# InkTime_Schematic.net
KiCad netlist of a schematic drawn in EAGLE
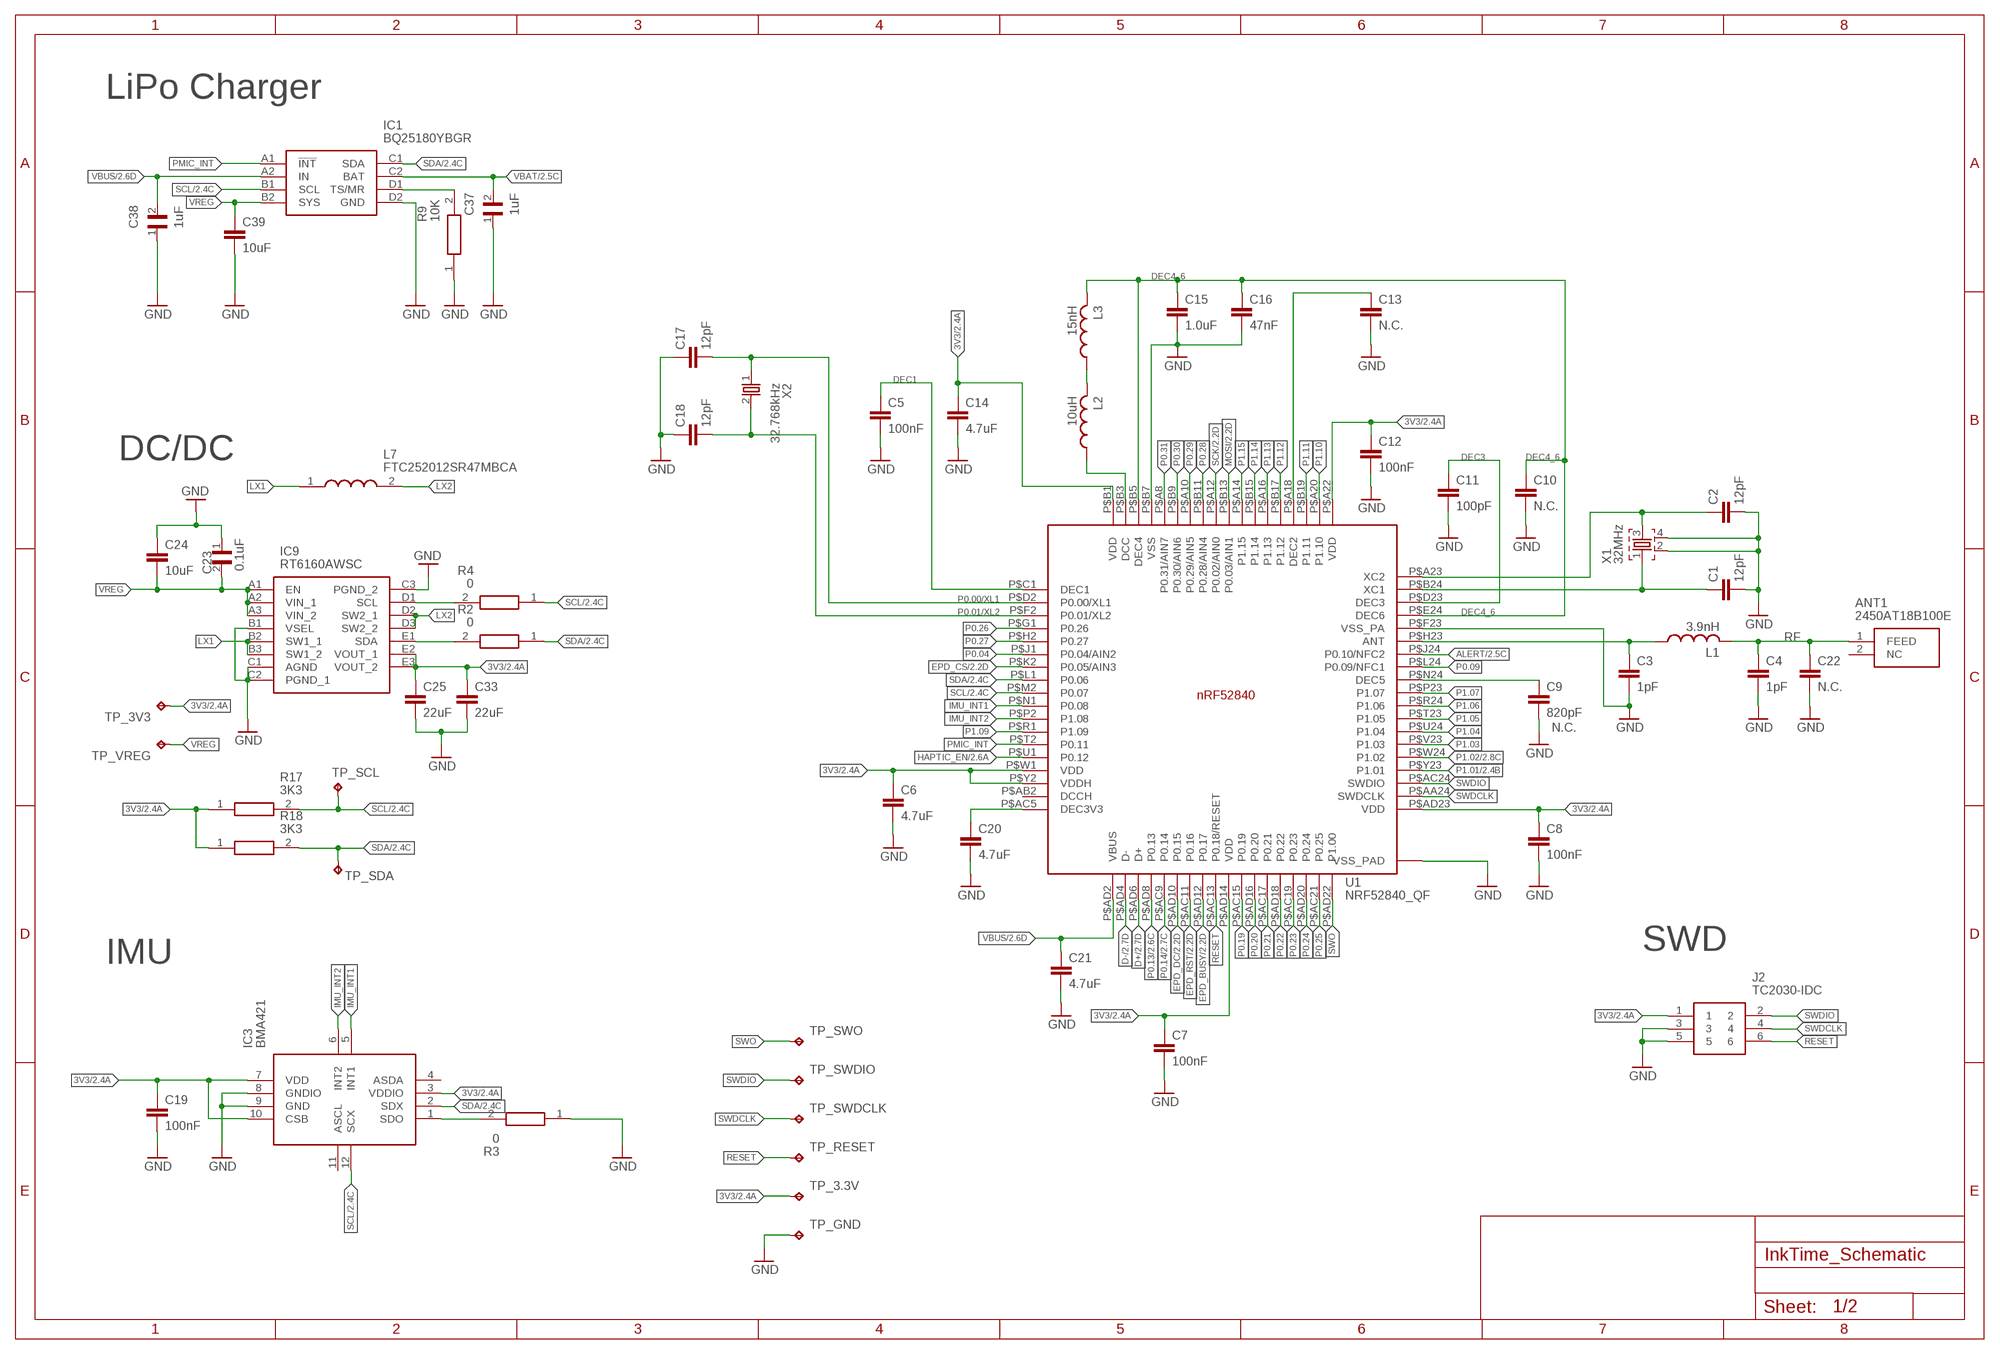
[diagram p0: schematic, sheet 1]
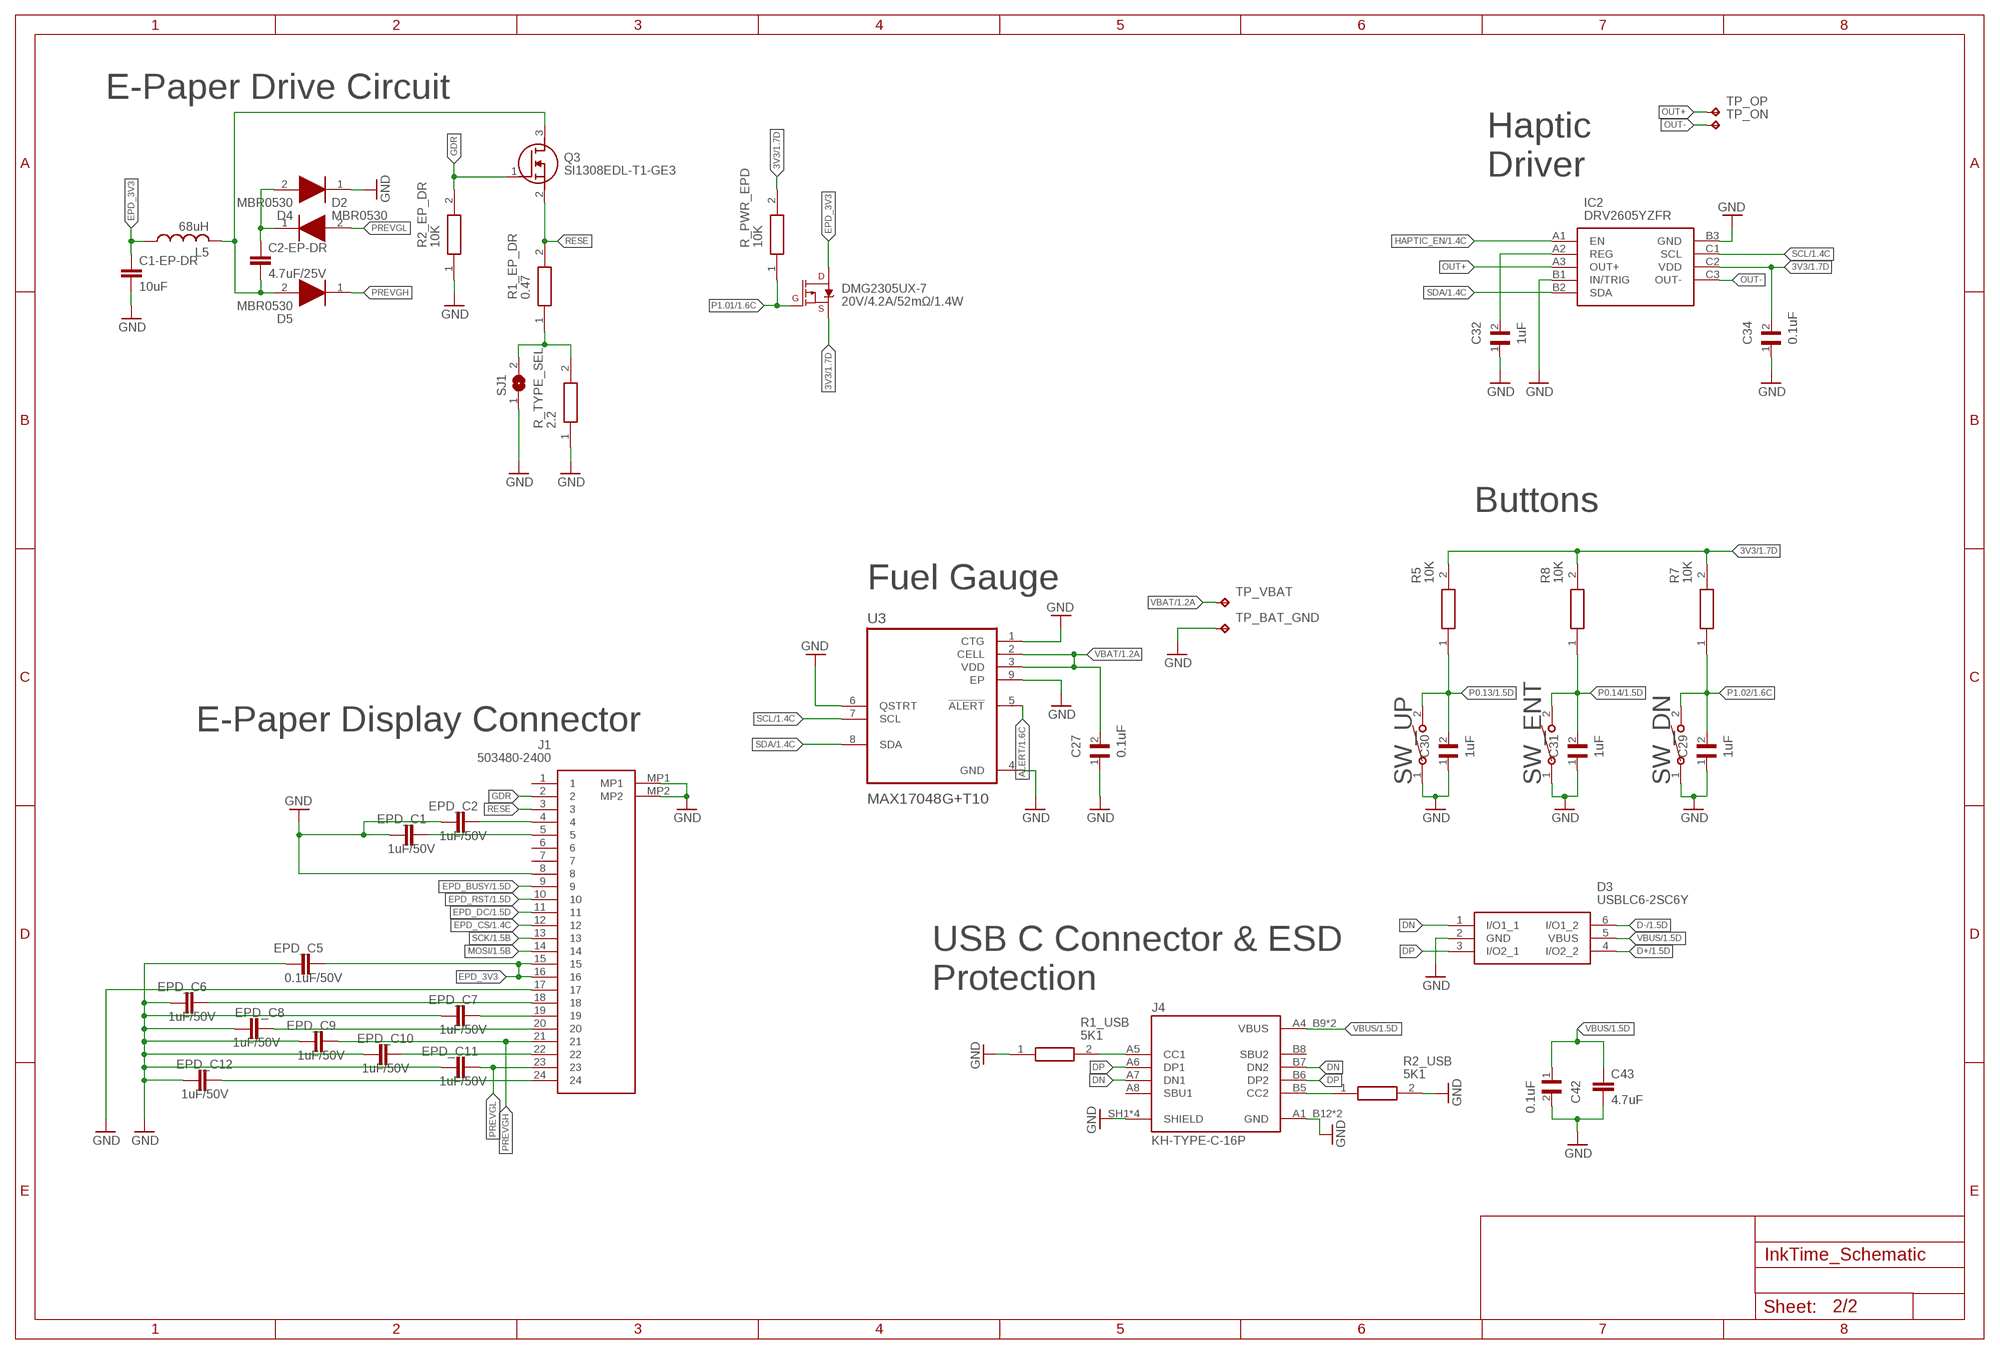
[diagram p1: schematic, sheet 2]

(export (version "E")
  (design (tool "Eeschema 10.0.6"))
  (components
    (comp (ref "ANT1")
      (value "2450AT18B100E")
      (footprint "eagle-import:2450AT18B100E_ANTC3216X140N")
      (fields (field (name "MOUSER_PART_NUMBER") "609-2450AT18B100E"))
      (libsource (lib "eagle-import") (part "2450AT18B100E_2450AT18B100E"))
    )
    (comp (ref "C1")
      (value "12pF")
      (footprint "eagle-import:GRM011R60J152KE01L_2_CAPC0201X13N")
      (libsource (lib "eagle-import") (part "NORDIC_NRF_3_CAPACITOR_0201_L"))
    )
    (comp (ref "C2")
      (value "12pF")
      (footprint "eagle-import:GRM011R60J152KE01L_2_CAPC0201X13N")
      (libsource (lib "eagle-import") (part "NORDIC_NRF_3_CAPACITOR_0201_L"))
    )
    (comp (ref "C3")
      (value "1pF")
      (footprint "eagle-import:GRM011R60J152KE01L_2_CAPC0201X13N")
      (libsource (lib "eagle-import") (part "NORDIC_NRF_3_CAPACITOR_0201_L"))
    )
    (comp (ref "C4")
      (value "1pF")
      (footprint "eagle-import:GRM011R60J152KE01L_2_CAPC0201X13N")
      (libsource (lib "eagle-import") (part "NORDIC_NRF_3_CAPACITOR_0201_L"))
    )
    (comp (ref "C5")
      (value "100nF")
      (footprint "eagle-import:GRM011R60J152KE01L_2_CAPC0201X13N")
      (libsource (lib "eagle-import") (part "NORDIC_NRF_3_CAPACITOR_0201_L"))
    )
    (comp (ref "C6")
      (value "4.7uF")
      (footprint "eagle-import:NORDIC_NRF_3_RESC0402_L")
      (libsource (lib "eagle-import") (part "NORDIC_NRF_3_CAPACITOR_0402_L"))
    )
    (comp (ref "C7")
      (value "100nF")
      (footprint "eagle-import:GRM011R60J152KE01L_2_CAPC0201X13N")
      (libsource (lib "eagle-import") (part "NORDIC_NRF_3_CAPACITOR_0201_L"))
    )
    (comp (ref "C8")
      (value "100nF")
      (footprint "eagle-import:GRM011R60J152KE01L_2_CAPC0201X13N")
      (libsource (lib "eagle-import") (part "NORDIC_NRF_3_CAPACITOR_0201_L"))
    )
    (comp (ref "C9")
      (value "820pF")
      (footprint "eagle-import:GRM011R60J152KE01L_2_CAPC0201X13N")
      (libsource (lib "eagle-import") (part "NORDIC_NRF_3_CAPACITOR_0201_L"))
    )
    (comp (ref "C10")
      (value "N.C.")
      (footprint "eagle-import:GRM011R60J152KE01L_2_CAPC0201X13N")
      (libsource (lib "eagle-import") (part "NORDIC_NRF_3_CAPACITOR_0201_L"))
    )
    (comp (ref "C11")
      (value "100pF")
      (footprint "eagle-import:GRM011R60J152KE01L_2_CAPC0201X13N")
      (libsource (lib "eagle-import") (part "NORDIC_NRF_3_CAPACITOR_0201_L"))
    )
    (comp (ref "C12")
      (value "100nF")
      (footprint "eagle-import:GRM011R60J152KE01L_2_CAPC0201X13N")
      (libsource (lib "eagle-import") (part "NORDIC_NRF_3_CAPACITOR_0201_L"))
    )
    (comp (ref "C13")
      (value "N.C.")
      (footprint "eagle-import:GRM011R60J152KE01L_2_CAPC0201X13N")
      (libsource (lib "eagle-import") (part "NORDIC_NRF_3_CAPACITOR_0201_L"))
    )
    (comp (ref "C14")
      (value "4.7uF")
      (footprint "eagle-import:NORDIC_NRF_3_RESC0402_L")
      (libsource (lib "eagle-import") (part "NORDIC_NRF_3_CAPACITOR_0402_L"))
    )
    (comp (ref "C15")
      (value "1.0uF")
      (footprint "eagle-import:NORDIC_NRF_3_RESC0402_L")
      (libsource (lib "eagle-import") (part "NORDIC_NRF_3_CAPACITOR_0402_L"))
    )
    (comp (ref "C16")
      (value "47nF")
      (footprint "eagle-import:GRM011R60J152KE01L_2_CAPC0201X13N")
      (libsource (lib "eagle-import") (part "NORDIC_NRF_3_CAPACITOR_0201_L"))
    )
    (comp (ref "C17")
      (value "12pF")
      (footprint "eagle-import:GRM011R60J152KE01L_2_CAPC0201X13N")
      (libsource (lib "eagle-import") (part "NORDIC_NRF_3_CAPACITOR_0201_L"))
    )
    (comp (ref "C18")
      (value "12pF")
      (footprint "eagle-import:GRM011R60J152KE01L_2_CAPC0201X13N")
      (libsource (lib "eagle-import") (part "NORDIC_NRF_3_CAPACITOR_0201_L"))
    )
    (comp (ref "C19")
      (value "100nF")
      (footprint "eagle-import:GRM011R60J152KE01L_2_CAPC0201X13N")
      (libsource (lib "eagle-import") (part "NORDIC_NRF_3_CAPACITOR_0201_L"))
    )
    (comp (ref "C20")
      (value "4.7uF")
      (footprint "eagle-import:NORDIC_NRF_3_RESC0402_L")
      (libsource (lib "eagle-import") (part "NORDIC_NRF_3_CAPACITOR_0402_L"))
    )
    (comp (ref "C21")
      (value "4.7uF")
      (footprint "eagle-import:NORDIC_NRF_3_RESC0402_L")
      (libsource (lib "eagle-import") (part "NORDIC_NRF_3_CAPACITOR_0402_L"))
    )
    (comp (ref "C22")
      (value "N.C.")
      (footprint "eagle-import:GRM011R60J152KE01L_2_CAPC0201X13N")
      (libsource (lib "eagle-import") (part "NORDIC_NRF_3_CAPACITOR_0201_L"))
    )
    (comp (ref "C23")
      (value "0.1uF")
      (footprint "eagle-import:GRM011R60J152KE01L_2_CAPC0201X13N")
      (fields (field (name "MF") "Murata") (field (name "MP") "GRM011R60J152KE01L"))
      (libsource (lib "eagle-import") (part "GRM011R60J152KE01L_2_GRM011R60J152KE01L"))
    )
    (comp (ref "C24")
      (value "10uF")
      (footprint "eagle-import:NORDIC_NRF_3_RESC0402_L")
      (libsource (lib "eagle-import") (part "PERFECT_0402_CAP_0402"))
    )
    (comp (ref "C25")
      (value "22uF")
      (footprint "eagle-import:NORDIC_NRF_3_RESC0402_L")
      (libsource (lib "eagle-import") (part "PERFECT_0402_CAP_0402"))
    )
    (comp (ref "C33")
      (value "22uF")
      (footprint "eagle-import:NORDIC_NRF_3_RESC0402_L")
      (libsource (lib "eagle-import") (part "PERFECT_0402_CAP_0402"))
    )
    (comp (ref "C37")
      (value "1uF")
      (footprint "eagle-import:GRM011R60J152KE01L_2_CAPC0201X13N")
      (fields (field (name "MF") "Murata") (field (name "MP") "GRM011R60J152KE01L"))
      (libsource (lib "eagle-import") (part "GRM011R60J152KE01L_2_GRM011R60J152KE01L"))
    )
    (comp (ref "C38")
      (value "1uF")
      (footprint "eagle-import:GRM011R60J152KE01L_2_CAPC0201X13N")
      (fields (field (name "MF") "Murata") (field (name "MP") "GRM011R60J152KE01L"))
      (libsource (lib "eagle-import") (part "GRM011R60J152KE01L_2_GRM011R60J152KE01L"))
    )
    (comp (ref "C39")
      (value "10uF")
      (footprint "eagle-import:NORDIC_NRF_3_RESC0402_L")
      (libsource (lib "eagle-import") (part "PERFECT_0402_CAP_0402"))
    )
    (comp (ref "IC1")
      (value "BQ25180YBGR")
      (footprint "eagle-import:BQ25180YBGR_BGA8C40P2X4_100X155X50")
      (fields (field (name "MOUSER_PART_NUMBER") "595-BQ25180YBGR"))
      (libsource (lib "eagle-import") (part "BQ25180YBGR_BQ25180YBGR"))
    )
    (comp (ref "IC3")
      (value "BMA421")
      (footprint "eagle-import:BMA423_BMA423")
      (fields (field (name "ARROW_PART_NUMBER") "BMA423") (field (name "MOUSER_PART_NUMBER") "262-BMA423"))
      (libsource (lib "eagle-import") (part "BMA423_BMA423"))
    )
    (comp (ref "IC9")
      (value "RT6160AWSC")
      (footprint "eagle-import:RT6160AWSC_BGA15C40P3X5_140X230X60")
      (fields (field (name "MOUSER_PART_NUMBER") "835-RT6160AWSC"))
      (libsource (lib "eagle-import") (part "RT6160AWSC_RT6160AWSC"))
    )
    (comp (ref "J2")
      (value "TC2030-IDC")
      (footprint "eagle-import:TC2030-IDC_TC2030IDC")
      (libsource (lib "eagle-import") (part "TC2030-IDC_TC2030-IDC"))
    )
    (comp (ref "L1")
      (value "3.9nH")
      (footprint "eagle-import:NORDIC_NRF_2_RESC0201_L")
      (libsource (lib "eagle-import") (part "NORDIC_NRF_2_INDUCTOR_0201_L"))
    )
    (comp (ref "L2")
      (value "10uH")
      (footprint "eagle-import:NORDIC_NRF_2_RESC0201_L")
      (libsource (lib "eagle-import") (part "NORDIC_NRF_2_INDUCTOR_0201_L"))
    )
    (comp (ref "L3")
      (value "15nH")
      (footprint "eagle-import:NORDIC_NRF_2_RESC0201_L")
      (libsource (lib "eagle-import") (part "NORDIC_NRF_2_INDUCTOR_0201_L"))
    )
    (comp (ref "L7")
      (value "FTC252012SR47MBCA")
      (footprint "eagle-import:MLP2016SR47MT0S1_INDC2016X100N")
      (libsource (lib "eagle-import") (part "MLP2016SR47MT0S1_FTC252012SR47MBCA"))
    )
    (comp (ref "R2")
      (value "0")
      (footprint "eagle-import:CPF0201D7K68C1_0201")
      (libsource (lib "eagle-import") (part "CPF0201D7K68C1_CPF0201D7K68C1"))
    )
    (comp (ref "R3")
      (value "0")
      (footprint "eagle-import:CPF0201D7K68C1_0201")
      (libsource (lib "eagle-import") (part "CPF0201D7K68C1_CPF0201D7K68C1"))
    )
    (comp (ref "R4")
      (value "0")
      (footprint "eagle-import:CPF0201D7K68C1_0201")
      (libsource (lib "eagle-import") (part "CPF0201D7K68C1_CPF0201D7K68C1"))
    )
    (comp (ref "R9")
      (value "10K")
      (footprint "eagle-import:CPF0201D7K68C1_0201")
      (libsource (lib "eagle-import") (part "CPF0201D7K68C1_CPF0201D7K68C1"))
    )
    (comp (ref "R17")
      (value "3K3")
      (footprint "eagle-import:CPF0201D7K68C1_0201")
      (libsource (lib "eagle-import") (part "CPF0201D7K68C1_CPF0201D7K68C1"))
    )
    (comp (ref "R18")
      (value "3K3")
      (footprint "eagle-import:CPF0201D7K68C1_0201")
      (libsource (lib "eagle-import") (part "CPF0201D7K68C1_CPF0201D7K68C1"))
    )
    (comp (ref "TP_3.3V")
      (value "HECTOR_WATCH_1_TPTP20R")
      (footprint "eagle-import:HECTOR_WATCH_1_TP20R")
      (libsource (lib "eagle-import") (part "HECTOR_WATCH_1_TPTP20R"))
    )
    (comp (ref "TP_3V3")
      (value "HECTOR_WATCH_1_TPTP20R")
      (footprint "eagle-import:HECTOR_WATCH_1_TP20R")
      (libsource (lib "eagle-import") (part "HECTOR_WATCH_1_TPTP20R"))
    )
    (comp (ref "TP_GND")
      (value "HECTOR_WATCH_1_TPTP20R")
      (footprint "eagle-import:HECTOR_WATCH_1_TP20R")
      (libsource (lib "eagle-import") (part "HECTOR_WATCH_1_TPTP20R"))
    )
    (comp (ref "TP_RESET")
      (value "HECTOR_WATCH_1_TPTP20R")
      (footprint "eagle-import:HECTOR_WATCH_1_TP20R")
      (libsource (lib "eagle-import") (part "HECTOR_WATCH_1_TPTP20R"))
    )
    (comp (ref "TP_SCL")
      (value "HECTOR_WATCH_1_TPTP20R")
      (footprint "eagle-import:HECTOR_WATCH_1_TP20R")
      (libsource (lib "eagle-import") (part "HECTOR_WATCH_1_TPTP20R"))
    )
    (comp (ref "TP_SDA")
      (value "HECTOR_WATCH_1_TPTP20R")
      (footprint "eagle-import:HECTOR_WATCH_1_TP20R")
      (libsource (lib "eagle-import") (part "HECTOR_WATCH_1_TPTP20R"))
    )
    (comp (ref "TP_SWDCLK")
      (value "HECTOR_WATCH_1_TPTP20R")
      (footprint "eagle-import:HECTOR_WATCH_1_TP20R")
      (libsource (lib "eagle-import") (part "HECTOR_WATCH_1_TPTP20R"))
    )
    (comp (ref "TP_SWDIO")
      (value "HECTOR_WATCH_1_TPTP20R")
      (footprint "eagle-import:HECTOR_WATCH_1_TP20R")
      (libsource (lib "eagle-import") (part "HECTOR_WATCH_1_TPTP20R"))
    )
    (comp (ref "TP_SWO")
      (value "HECTOR_WATCH_1_TPTP20R")
      (footprint "eagle-import:HECTOR_WATCH_1_TP20R")
      (libsource (lib "eagle-import") (part "HECTOR_WATCH_1_TPTP20R"))
    )
    (comp (ref "TP_VREG")
      (value "HECTOR_WATCH_1_TPTP20R")
      (footprint "eagle-import:HECTOR_WATCH_1_TP20R")
      (libsource (lib "eagle-import") (part "HECTOR_WATCH_1_TPTP20R"))
    )
    (comp (ref "U1")
      (value "NRF52840_QF")
      (footprint "eagle-import:NORDIC_NRF_4_AQFN50P700X700X85_HS-74N")
      (libsource (lib "eagle-import") (part "NORDIC_NRF_4_NRF52840_QF"))
    )
    (comp (ref "X1")
      (value "32MHz")
      (footprint "eagle-import:NORDIC_NRF_BT-XTAL_2016_N")
      (libsource (lib "eagle-import") (part "NORDIC_NRF_XTAL_32MHZ"))
    )
    (comp (ref "X2")
      (value "32.768kHz")
      (footprint "eagle-import:NORDIC_NRF_1_XTAL_3215_N")
      (libsource (lib "eagle-import") (part "NORDIC_NRF_1_XTAL_32KHZ"))
    )
    (comp (ref "C1-EP-DR")
      (value "10uF")
      (footprint "eagle-import:GRM011R60J152KE01L_2_CAPC0201X13N")
      (libsource (lib "eagle-import") (part "NORDIC_NRF_3_CAPACITOR_0201_L"))
    )
    (comp (ref "C2-EP-DR")
      (value "4.7uF/25V")
      (footprint "eagle-import:NORDIC_NRF_3_RESC0402_L")
      (libsource (lib "eagle-import") (part "PERFECT_0402_CAP_0402"))
    )
    (comp (ref "C27")
      (value "0.1uF")
      (footprint "eagle-import:GRM011R60J152KE01L_2_CAPC0201X13N")
      (fields (field (name "MF") "Murata") (field (name "MP") "GRM011R60J152KE01L"))
      (libsource (lib "eagle-import") (part "GRM011R60J152KE01L_2_GRM011R60J152KE01L"))
    )
    (comp (ref "C29")
      (value "1uF")
      (footprint "eagle-import:GRM011R60J152KE01L_2_CAPC0201X13N")
      (fields (field (name "MF") "Murata") (field (name "MP") "GRM011R60J152KE01L"))
      (libsource (lib "eagle-import") (part "GRM011R60J152KE01L_2_GRM011R60J152KE01L"))
    )
    (comp (ref "C30")
      (value "1uF")
      (footprint "eagle-import:GRM011R60J152KE01L_2_CAPC0201X13N")
      (fields (field (name "MF") "Murata") (field (name "MP") "GRM011R60J152KE01L"))
      (libsource (lib "eagle-import") (part "GRM011R60J152KE01L_2_GRM011R60J152KE01L"))
    )
    (comp (ref "C31")
      (value "1uF")
      (footprint "eagle-import:GRM011R60J152KE01L_2_CAPC0201X13N")
      (fields (field (name "MF") "Murata") (field (name "MP") "GRM011R60J152KE01L"))
      (libsource (lib "eagle-import") (part "GRM011R60J152KE01L_2_GRM011R60J152KE01L"))
    )
    (comp (ref "C32")
      (value "1uF")
      (footprint "eagle-import:GRM011R60J152KE01L_2_CAPC0201X13N")
      (fields (field (name "MF") "Murata") (field (name "MP") "GRM011R60J152KE01L"))
      (libsource (lib "eagle-import") (part "GRM011R60J152KE01L_2_GRM011R60J152KE01L"))
    )
    (comp (ref "C34")
      (value "0.1uF")
      (footprint "eagle-import:GRM011R60J152KE01L_2_CAPC0201X13N")
      (fields (field (name "MF") "Murata") (field (name "MP") "GRM011R60J152KE01L"))
      (libsource (lib "eagle-import") (part "GRM011R60J152KE01L_2_GRM011R60J152KE01L"))
    )
    (comp (ref "C42")
      (value "0.1uF")
      (footprint "eagle-import:GRM011R60J152KE01L_2_CAPC0201X13N")
      (fields (field (name "MF") "Murata") (field (name "MP") "GRM011R60J152KE01L"))
      (libsource (lib "eagle-import") (part "GRM011R60J152KE01L_2_GRM011R60J152KE01L"))
    )
    (comp (ref "C43")
      (value "4.7uF")
      (footprint "eagle-import:NORDIC_NRF_3_RESC0402_L")
      (libsource (lib "eagle-import") (part "NORDIC_NRF_3_CAPACITOR_0402_L"))
    )
    (comp (ref "D2")
      (value "MBR0530")
      (footprint "eagle-import:ESP32_C6_LIBRARY_5_SOD3716X135N")
      (fields (field (name "MF") "ON Semiconductor"))
      (libsource (lib "eagle-import") (part "ESP32_C6_LIBRARY_5_MBR0530"))
    )
    (comp (ref "D3")
      (value "USBLC6-2SC6Y")
      (footprint "eagle-import:ESP32_C6_LIBRARY_3_SOT95P280X145-6N")
      (fields (field (name "MF") "STMicroelectronics"))
      (libsource (lib "eagle-import") (part "ESP32_C6_LIBRARY_3_USBLC6-2SC6Y"))
    )
    (comp (ref "D4")
      (value "MBR0530")
      (footprint "eagle-import:ESP32_C6_LIBRARY_5_SOD3716X135N")
      (fields (field (name "MF") "ON Semiconductor"))
      (libsource (lib "eagle-import") (part "ESP32_C6_LIBRARY_5_MBR0530"))
    )
    (comp (ref "D5")
      (value "MBR0530")
      (footprint "eagle-import:ESP32_C6_LIBRARY_5_SOD3716X135N")
      (fields (field (name "MF") "ON Semiconductor"))
      (libsource (lib "eagle-import") (part "ESP32_C6_LIBRARY_5_MBR0530"))
    )
    (comp (ref "DMG2305UX-7")
      (value "20V/4.2A/52mΩ/1.4W")
      (footprint "eagle-import:ESP32_C6_LIBRARY_4_ESP32_C6_LIBRARY_4_ESP32_C6_LIBRARY_4_ESP32_C6_LIBRARY_4_ESP32_WROVER_SPARKFUN-DISCRETESEMI_SOT23-3")
      (libsource (lib "eagle-import") (part "ESP32_C6_LIBRARY_4_ESP32_WROVER_SPARKFUN-DISCRETESEMI_MOSFET_PCH-DMG2305UX-7"))
    )
    (comp (ref "EPD_C1")
      (value "1uF/50V")
      (footprint "eagle-import:NORDIC_NRF_3_RESC0402_L")
      (libsource (lib "eagle-import") (part "NORDIC_NRF_3_CAPACITOR_0402_L"))
    )
    (comp (ref "EPD_C2")
      (value "1uF/50V")
      (footprint "eagle-import:NORDIC_NRF_3_RESC0402_L")
      (libsource (lib "eagle-import") (part "NORDIC_NRF_3_CAPACITOR_0402_L"))
    )
    (comp (ref "EPD_C5")
      (value "0.1uF/50V")
      (footprint "eagle-import:GRM011R60J152KE01L_2_CAPC0201X13N")
      (libsource (lib "eagle-import") (part "NORDIC_NRF_3_CAPACITOR_0201_L"))
    )
    (comp (ref "EPD_C6")
      (value "1uF/50V")
      (footprint "eagle-import:NORDIC_NRF_3_RESC0402_L")
      (libsource (lib "eagle-import") (part "NORDIC_NRF_3_CAPACITOR_0402_L"))
    )
    (comp (ref "EPD_C7")
      (value "1uF/50V")
      (footprint "eagle-import:NORDIC_NRF_3_RESC0402_L")
      (libsource (lib "eagle-import") (part "NORDIC_NRF_3_CAPACITOR_0402_L"))
    )
    (comp (ref "EPD_C8")
      (value "1uF/50V")
      (footprint "eagle-import:NORDIC_NRF_3_RESC0402_L")
      (libsource (lib "eagle-import") (part "NORDIC_NRF_3_CAPACITOR_0402_L"))
    )
    (comp (ref "EPD_C9")
      (value "1uF/50V")
      (footprint "eagle-import:NORDIC_NRF_3_RESC0402_L")
      (libsource (lib "eagle-import") (part "NORDIC_NRF_3_CAPACITOR_0402_L"))
    )
    (comp (ref "EPD_C10")
      (value "1uF/50V")
      (footprint "eagle-import:NORDIC_NRF_3_RESC0402_L")
      (libsource (lib "eagle-import") (part "NORDIC_NRF_3_CAPACITOR_0402_L"))
    )
    (comp (ref "EPD_C11")
      (value "1uF/50V")
      (footprint "eagle-import:NORDIC_NRF_3_RESC0402_L")
      (libsource (lib "eagle-import") (part "NORDIC_NRF_3_CAPACITOR_0402_L"))
    )
    (comp (ref "EPD_C12")
      (value "1uF/50V")
      (footprint "eagle-import:NORDIC_NRF_3_RESC0402_L")
      (libsource (lib "eagle-import") (part "NORDIC_NRF_3_CAPACITOR_0402_L"))
    )
    (comp (ref "IC2")
      (value "DRV2605YZFR")
      (footprint "eagle-import:DRV2605YZFR_BGA9C50P3X3_144X144X62")
      (libsource (lib "eagle-import") (part "DRV2605YZFR_DRV2605YZFR"))
    )
    (comp (ref "J1")
      (value "503480-2400")
      (footprint "eagle-import:503480-2400_5034802400")
      (fields (field (name "MOUSER_PART_NUMBER") "538-503480-2400"))
      (libsource (lib "eagle-import") (part "503480-2400_503480-2400"))
    )
    (comp (ref "J4")
      (value "KH-TYPE-C-16P")
      (footprint "eagle-import:KH-TYPE-C-16P_KINGHELM_KH-TYPE-C-16P")
      (fields (field (name "MF") "kinghelm"))
      (libsource (lib "eagle-import") (part "KH-TYPE-C-16P_KH-TYPE-C-16P"))
    )
    (comp (ref "L5")
      (value "68uH")
      (footprint "eagle-import:NORDIC_NRF_2_RESC0201_L")
      (libsource (lib "eagle-import") (part "NORDIC_NRF_2_INDUCTOR_0201_L"))
    )
    (comp (ref "Q3")
      (value "SI1308EDL-T1-GE3")
      (footprint "eagle-import:ESP32_C6_LIBRARY_6_SOT65P210X110-3N")
      (fields (field (name "MF") "Vishay Siliconix"))
      (libsource (lib "eagle-import") (part "ESP32_C6_LIBRARY_6_SI1308EDL-T1-GE3"))
    )
    (comp (ref "R1_EP_DR")
      (value "0.47")
      (footprint "eagle-import:CPF0201D7K68C1_0201")
      (libsource (lib "eagle-import") (part "CPF0201D7K68C1_CPF0201D7K68C1"))
    )
    (comp (ref "R1_USB")
      (value "5K1")
      (footprint "eagle-import:CPF0201D7K68C1_0201")
      (libsource (lib "eagle-import") (part "CPF0201D7K68C1_CPF0201D7K68C1"))
    )
    (comp (ref "R2_EP_DR")
      (value "10K")
      (footprint "eagle-import:CPF0201D7K68C1_0201")
      (libsource (lib "eagle-import") (part "CPF0201D7K68C1_CPF0201D7K68C1"))
    )
    (comp (ref "R2_USB")
      (value "5K1")
      (footprint "eagle-import:CPF0201D7K68C1_0201")
      (libsource (lib "eagle-import") (part "CPF0201D7K68C1_CPF0201D7K68C1"))
    )
    (comp (ref "R5")
      (value "10K")
      (footprint "eagle-import:CPF0201D7K68C1_0201")
      (libsource (lib "eagle-import") (part "CPF0201D7K68C1_CPF0201D7K68C1"))
    )
    (comp (ref "R7")
      (value "10K")
      (footprint "eagle-import:CPF0201D7K68C1_0201")
      (libsource (lib "eagle-import") (part "CPF0201D7K68C1_CPF0201D7K68C1"))
    )
    (comp (ref "R8")
      (value "10K")
      (footprint "eagle-import:CPF0201D7K68C1_0201")
      (libsource (lib "eagle-import") (part "CPF0201D7K68C1_CPF0201D7K68C1"))
    )
    (comp (ref "R_PWR_EPD")
      (value "10K")
      (footprint "eagle-import:CPF0201D7K68C1_0201")
      (libsource (lib "eagle-import") (part "CPF0201D7K68C1_CPF0201D7K68C1"))
    )
    (comp (ref "R_TYPE_SEL")
      (value "2.2")
      (footprint "eagle-import:CPF0201D7K68C1_0201")
      (libsource (lib "eagle-import") (part "CPF0201D7K68C1_CPF0201D7K68C1"))
    )
    (comp (ref "SJ1")
      (value "ESP32_C6_LIBRARY_7_JUMPER_SJ")
      (footprint "eagle-import:ESP32_C6_LIBRARY_7_JUMPER_SJ")
      (libsource (lib "eagle-import") (part "ESP32_C6_LIBRARY_7_JUMPER_SJ"))
    )
    (comp (ref "SW_DN")
      (value "2025-10-22_07-23-44_LIBRARY_EVP-AKE31ASW_EVP-AKE31A_PAN")
      (footprint "eagle-import:2025-10-22_07-23-44_LIBRARY_SW_EVP-AKE31A_PAN")
      (fields
        (field (name "MANUFACTURER_PART_NUMBER") "EVP-AKE31A")
        (field (name "COPYRIGHT") "Copyright (C) 2025 Ultra Librarian. All rights reserved.")
      )
      (libsource (lib "eagle-import") (part "2025-10-22_07-23-44_LIBRARY_EVP-AKE31ASW_EVP-AKE31A_PAN"))
    )
    (comp (ref "SW_ENT")
      (value "2025-10-22_07-23-44_LIBRARY_EVP-AKE31ASW_EVP-AKE31A_PAN")
      (footprint "eagle-import:2025-10-22_07-23-44_LIBRARY_SW_EVP-AKE31A_PAN")
      (fields
        (field (name "MANUFACTURER_PART_NUMBER") "EVP-AKE31A")
        (field (name "COPYRIGHT") "Copyright (C) 2025 Ultra Librarian. All rights reserved.")
      )
      (libsource (lib "eagle-import") (part "2025-10-22_07-23-44_LIBRARY_EVP-AKE31ASW_EVP-AKE31A_PAN"))
    )
    (comp (ref "SW_UP")
      (value "2025-10-22_07-23-44_LIBRARY_EVP-AKE31ASW_EVP-AKE31A_PAN")
      (footprint "eagle-import:2025-10-22_07-23-44_LIBRARY_SW_EVP-AKE31A_PAN")
      (fields
        (field (name "MANUFACTURER_PART_NUMBER") "EVP-AKE31A")
        (field (name "COPYRIGHT") "Copyright (C) 2025 Ultra Librarian. All rights reserved.")
      )
      (libsource (lib "eagle-import") (part "2025-10-22_07-23-44_LIBRARY_EVP-AKE31ASW_EVP-AKE31A_PAN"))
    )
    (comp (ref "TP_BAT_GND")
      (value "HECTOR_WATCH_1_TPTP20R")
      (footprint "eagle-import:HECTOR_WATCH_1_TP20R")
      (libsource (lib "eagle-import") (part "HECTOR_WATCH_1_TPTP20R"))
    )
    (comp (ref "TP_ON")
      (value "HECTOR_WATCH_1_TPTP20R")
      (footprint "eagle-import:HECTOR_WATCH_1_TP20R")
      (libsource (lib "eagle-import") (part "HECTOR_WATCH_1_TPTP20R"))
    )
    (comp (ref "TP_OP")
      (value "HECTOR_WATCH_1_TPTP20R")
      (footprint "eagle-import:HECTOR_WATCH_1_TP20R")
      (libsource (lib "eagle-import") (part "HECTOR_WATCH_1_TPTP20R"))
    )
    (comp (ref "TP_VBAT")
      (value "HECTOR_WATCH_1_TPTP20R")
      (footprint "eagle-import:HECTOR_WATCH_1_TP20R")
      (libsource (lib "eagle-import") (part "HECTOR_WATCH_1_TPTP20R"))
    )
    (comp (ref "U3")
      (value "MAX17048G+T10")
      (footprint "eagle-import:ESP32_C6_LIBRARY_SON50P200X200X80-9N")
      (fields (field (name "MF") "Analog Devices"))
      (libsource (lib "eagle-import") (part "ESP32_C6_LIBRARY_MAX17048G+T10"))
    )
  )
  (nets
    (net (code "1") (name "3V3{slash}1.7D") (class "Default")
      (node (ref "C34") (pin "2") (pinfunction "2_2") (pintype "passive"))
      (node (ref "DMG2305UX-7") (pin "2") (pinfunction "S_2") (pintype "bidirectional"))
      (node (ref "IC2") (pin "C2") (pinfunction "VDD_C2") (pintype "bidirectional"))
      (node (ref "R5") (pin "2") (pinfunction "2_2") (pintype "bidirectional"))
      (node (ref "R7") (pin "2") (pinfunction "2_2") (pintype "bidirectional"))
      (node (ref "R8") (pin "2") (pinfunction "2_2") (pintype "bidirectional"))
      (node (ref "R_PWR_EPD") (pin "2") (pinfunction "2_2") (pintype "bidirectional"))
    )
    (net (code "2") (name "3V3{slash}2.4A") (class "Default")
      (node (ref "C12") (pin "1") (pinfunction "1_1") (pintype "passive"))
      (node (ref "C14") (pin "1") (pinfunction "1_1") (pintype "passive"))
      (node (ref "C19") (pin "1") (pinfunction "1_1") (pintype "passive"))
      (node (ref "C25") (pin "1") (pinfunction "1_1") (pintype "passive"))
      (node (ref "C33") (pin "1") (pinfunction "1_1") (pintype "passive"))
      (node (ref "C6") (pin "1") (pinfunction "1_1") (pintype "passive"))
      (node (ref "C7") (pin "1") (pinfunction "1_1") (pintype "passive"))
      (node (ref "C8") (pin "1") (pinfunction "1_1") (pintype "passive"))
      (node (ref "IC3") (pin "10") (pinfunction "CSB_10") (pintype "bidirectional"))
      (node (ref "IC3") (pin "3") (pinfunction "VDDIO_3") (pintype "bidirectional"))
      (node (ref "IC3") (pin "7") (pinfunction "VDD_7") (pintype "bidirectional"))
      (node (ref "IC9") (pin "E2") (pinfunction "VOUT_1_E2") (pintype "bidirectional"))
      (node (ref "IC9") (pin "E3") (pinfunction "VOUT_2_E3") (pintype "bidirectional"))
      (node (ref "J2") (pin "1") (pinfunction "1_1") (pintype "bidirectional"))
      (node (ref "R17") (pin "1") (pinfunction "1_1") (pintype "bidirectional"))
      (node (ref "R18") (pin "1") (pinfunction "1_1") (pintype "bidirectional"))
      (node (ref "TP_3.3V") (pin "TP") (pinfunction "TP_TP") (pintype "input"))
      (node (ref "TP_3V3") (pin "TP") (pinfunction "TP_TP") (pintype "input"))
      (node (ref "U1") (pin "P$A22") (pinfunction "VDD_P$A22") (pintype "power_in"))
      (node (ref "U1") (pin "P$AD14") (pinfunction "VDD_P$AD14") (pintype "power_in"))
      (node (ref "U1") (pin "P$AD23") (pinfunction "VDD_P$AD23") (pintype "power_in"))
      (node (ref "U1") (pin "P$B1") (pinfunction "VDD_P$B1") (pintype "power_in"))
      (node (ref "U1") (pin "P$W1") (pinfunction "VDD_P$W1") (pintype "power_in"))
      (node (ref "U1") (pin "P$Y2") (pinfunction "VDDH_P$Y2") (pintype "power_in"))
    )
    (net (code "3") (name "ALERT{slash}1.6C") (class "Default")
      (node (ref "U3") (pin "5") (pinfunction "~{ALERT}_5") (pintype "output"))
    )
    (net (code "4") (name "ALERT{slash}2.5C") (class "Default")
      (node (ref "U1") (pin "P$J24") (pinfunction "P0.10/NFC2_P$J24") (pintype "bidirectional"))
    )
    (net (code "5") (name "D+{slash}1.5D") (class "Default")
      (node (ref "D3") (pin "4") (pinfunction "I/O2_2_4") (pintype "bidirectional"))
    )
    (net (code "6") (name "D+{slash}2.7D") (class "Default")
      (node (ref "U1") (pin "P$AD6") (pinfunction "D+_P$AD6") (pintype "bidirectional"))
    )
    (net (code "7") (name "D-{slash}1.5D") (class "Default")
      (node (ref "D3") (pin "6") (pinfunction "I/O1_2_6") (pintype "bidirectional"))
    )
    (net (code "8") (name "D-{slash}2.7D") (class "Default")
      (node (ref "U1") (pin "P$AD4") (pinfunction "D-_P$AD4") (pintype "bidirectional"))
    )
    (net (code "9") (name "DEC1") (class "Default")
      (node (ref "C5") (pin "1") (pinfunction "1_1") (pintype "passive"))
      (node (ref "U1") (pin "P$C1") (pinfunction "DEC1_P$C1") (pintype "power_in"))
    )
    (net (code "10") (name "DEC3") (class "Default")
      (node (ref "C11") (pin "1") (pinfunction "1_1") (pintype "passive"))
      (node (ref "U1") (pin "P$D23") (pinfunction "DEC3_P$D23") (pintype "bidirectional"))
    )
    (net (code "11") (name "DEC4_6") (class "Default")
      (node (ref "C10") (pin "1") (pinfunction "1_1") (pintype "passive"))
      (node (ref "C15") (pin "1") (pinfunction "1_1") (pintype "passive"))
      (node (ref "C16") (pin "1") (pinfunction "1_1") (pintype "passive"))
      (node (ref "L3") (pin "2") (pinfunction "2_2") (pintype "passive"))
      (node (ref "U1") (pin "P$B5") (pinfunction "DEC4_P$B5") (pintype "power_in"))
      (node (ref "U1") (pin "P$E24") (pinfunction "DEC6_P$E24") (pintype "bidirectional"))
    )
    (net (code "12") (name "DN") (class "Default")
      (node (ref "D3") (pin "1") (pinfunction "I/O1_1_1") (pintype "bidirectional"))
      (node (ref "J4") (pin "A7") (pinfunction "DN1_A7") (pintype "bidirectional"))
      (node (ref "J4") (pin "B7") (pinfunction "DN2_B7") (pintype "bidirectional"))
    )
    (net (code "13") (name "DP") (class "Default")
      (node (ref "D3") (pin "3") (pinfunction "I/O2_1_3") (pintype "bidirectional"))
      (node (ref "J4") (pin "A6") (pinfunction "DP1_A6") (pintype "bidirectional"))
      (node (ref "J4") (pin "B6") (pinfunction "DP2_B6") (pintype "bidirectional"))
    )
    (net (code "14") (name "EPD_3V3") (class "Default")
      (node (ref "C1-EP-DR") (pin "1") (pinfunction "1_1") (pintype "passive"))
      (node (ref "DMG2305UX-7") (pin "3") (pinfunction "D_3") (pintype "bidirectional"))
      (node (ref "EPD_C5") (pin "2") (pinfunction "2_2") (pintype "passive"))
      (node (ref "J1") (pin "15") (pinfunction "15_15") (pintype "bidirectional"))
      (node (ref "J1") (pin "16") (pinfunction "16_16") (pintype "bidirectional"))
      (node (ref "L5") (pin "1") (pinfunction "1_1") (pintype "passive"))
    )
    (net (code "15") (name "EPD_BUSY{slash}1.5D") (class "Default")
      (node (ref "J1") (pin "9") (pinfunction "9_9") (pintype "bidirectional"))
    )
    (net (code "16") (name "EPD_BUSY{slash}2.2D") (class "Default")
      (node (ref "U1") (pin "P$AD12") (pinfunction "P0.17_P$AD12") (pintype "bidirectional"))
    )
    (net (code "17") (name "EPD_CS{slash}1.4C") (class "Default")
      (node (ref "J1") (pin "12") (pinfunction "12_12") (pintype "bidirectional"))
    )
    (net (code "18") (name "EPD_CS{slash}2.2D") (class "Default")
      (node (ref "U1") (pin "P$K2") (pinfunction "P0.05/AIN3_P$K2") (pintype "bidirectional"))
    )
    (net (code "19") (name "EPD_DC{slash}1.5D") (class "Default")
      (node (ref "J1") (pin "11") (pinfunction "11_11") (pintype "bidirectional"))
    )
    (net (code "20") (name "EPD_DC{slash}2.2D") (class "Default")
      (node (ref "U1") (pin "P$AD10") (pinfunction "P0.15_P$AD10") (pintype "bidirectional"))
    )
    (net (code "21") (name "EPD_RST{slash}1.5D") (class "Default")
      (node (ref "J1") (pin "10") (pinfunction "10_10") (pintype "bidirectional"))
    )
    (net (code "22") (name "EPD_RST{slash}2.2D") (class "Default")
      (node (ref "U1") (pin "P$AC11") (pinfunction "P0.16_P$AC11") (pintype "bidirectional"))
    )
    (net (code "23") (name "GDR") (class "Default")
      (node (ref "J1") (pin "2") (pinfunction "2_2") (pintype "bidirectional"))
      (node (ref "Q3") (pin "1") (pinfunction "G_1") (pintype "bidirectional"))
      (node (ref "R2_EP_DR") (pin "2") (pinfunction "2_2") (pintype "bidirectional"))
    )
    (net (code "24") (name "GND") (class "Default")
      (node (ref "C1") (pin "2") (pinfunction "2_2") (pintype "passive"))
      (node (ref "C1-EP-DR") (pin "2") (pinfunction "2_2") (pintype "passive"))
      (node (ref "C10") (pin "2") (pinfunction "2_2") (pintype "passive"))
      (node (ref "C11") (pin "2") (pinfunction "2_2") (pintype "passive"))
      (node (ref "C12") (pin "2") (pinfunction "2_2") (pintype "passive"))
      (node (ref "C13") (pin "2") (pinfunction "2_2") (pintype "passive"))
      (node (ref "C14") (pin "2") (pinfunction "2_2") (pintype "passive"))
      (node (ref "C15") (pin "2") (pinfunction "2_2") (pintype "passive"))
      (node (ref "C16") (pin "2") (pinfunction "2_2") (pintype "passive"))
      (node (ref "C17") (pin "1") (pinfunction "1_1") (pintype "passive"))
      (node (ref "C18") (pin "1") (pinfunction "1_1") (pintype "passive"))
      (node (ref "C19") (pin "2") (pinfunction "2_2") (pintype "passive"))
      (node (ref "C2") (pin "2") (pinfunction "2_2") (pintype "passive"))
      (node (ref "C20") (pin "2") (pinfunction "2_2") (pintype "passive"))
      (node (ref "C21") (pin "2") (pinfunction "2_2") (pintype "passive"))
      (node (ref "C22") (pin "2") (pinfunction "2_2") (pintype "passive"))
      (node (ref "C23") (pin "1") (pinfunction "1_1") (pintype "passive"))
      (node (ref "C24") (pin "1") (pinfunction "1_1") (pintype "passive"))
      (node (ref "C25") (pin "2") (pinfunction "2_2") (pintype "passive"))
      (node (ref "C27") (pin "1") (pinfunction "1_1") (pintype "passive"))
      (node (ref "C29") (pin "1") (pinfunction "1_1") (pintype "passive"))
      (node (ref "C3") (pin "2") (pinfunction "2_2") (pintype "passive"))
      (node (ref "C30") (pin "1") (pinfunction "1_1") (pintype "passive"))
      (node (ref "C31") (pin "1") (pinfunction "1_1") (pintype "passive"))
      (node (ref "C32") (pin "1") (pinfunction "1_1") (pintype "passive"))
      (node (ref "C33") (pin "2") (pinfunction "2_2") (pintype "passive"))
      (node (ref "C34") (pin "1") (pinfunction "1_1") (pintype "passive"))
      (node (ref "C37") (pin "1") (pinfunction "1_1") (pintype "passive"))
      (node (ref "C38") (pin "1") (pinfunction "1_1") (pintype "passive"))
      (node (ref "C39") (pin "2") (pinfunction "2_2") (pintype "passive"))
      (node (ref "C4") (pin "2") (pinfunction "2_2") (pintype "passive"))
      (node (ref "C42") (pin "2") (pinfunction "2_2") (pintype "passive"))
      (node (ref "C43") (pin "2") (pinfunction "2_2") (pintype "passive"))
      (node (ref "C5") (pin "2") (pinfunction "2_2") (pintype "passive"))
      (node (ref "C6") (pin "2") (pinfunction "2_2") (pintype "passive"))
      (node (ref "C7") (pin "2") (pinfunction "2_2") (pintype "passive"))
      (node (ref "C8") (pin "2") (pinfunction "2_2") (pintype "passive"))
      (node (ref "C9") (pin "2") (pinfunction "2_2") (pintype "passive"))
      (node (ref "D3") (pin "2") (pinfunction "GND_2") (pintype "bidirectional"))
      (node (ref "D4") (pin "1") (pinfunction "K_1") (pintype "bidirectional"))
      (node (ref "EPD_C1") (pin "1") (pinfunction "1_1") (pintype "passive"))
      (node (ref "EPD_C10") (pin "1") (pinfunction "1_1") (pintype "passive"))
      (node (ref "EPD_C11") (pin "1") (pinfunction "1_1") (pintype "passive"))
      (node (ref "EPD_C12") (pin "1") (pinfunction "1_1") (pintype "passive"))
      (node (ref "EPD_C2") (pin "1") (pinfunction "1_1") (pintype "passive"))
      (node (ref "EPD_C5") (pin "1") (pinfunction "1_1") (pintype "passive"))
      (node (ref "EPD_C6") (pin "1") (pinfunction "1_1") (pintype "passive"))
      (node (ref "EPD_C7") (pin "1") (pinfunction "1_1") (pintype "passive"))
      (node (ref "EPD_C8") (pin "1") (pinfunction "1_1") (pintype "passive"))
      (node (ref "EPD_C9") (pin "1") (pinfunction "1_1") (pintype "passive"))
      (node (ref "IC1") (pin "D2") (pinfunction "GND_D2") (pintype "bidirectional"))
      (node (ref "IC2") (pin "B1") (pinfunction "IN/TRIG_B1") (pintype "bidirectional"))
      (node (ref "IC2") (pin "B3") (pinfunction "GND_B3") (pintype "bidirectional"))
      (node (ref "IC3") (pin "8") (pinfunction "GNDIO_8") (pintype "bidirectional"))
      (node (ref "IC3") (pin "9") (pinfunction "GND_9") (pintype "bidirectional"))
      (node (ref "IC9") (pin "B1") (pinfunction "VSEL_B1") (pintype "bidirectional"))
      (node (ref "IC9") (pin "C1") (pinfunction "AGND_C1") (pintype "bidirectional"))
      (node (ref "IC9") (pin "C2") (pinfunction "PGND_1_C2") (pintype "bidirectional"))
      (node (ref "IC9") (pin "C3") (pinfunction "PGND_2_C3") (pintype "bidirectional"))
      (node (ref "J1") (pin "17") (pinfunction "17_17") (pintype "bidirectional"))
      (node (ref "J1") (pin "8") (pinfunction "8_8") (pintype "bidirectional"))
      (node (ref "J1") (pin "MP1") (pinfunction "MP1_MP1") (pintype "bidirectional"))
      (node (ref "J1") (pin "MP2") (pinfunction "MP2_MP2") (pintype "bidirectional"))
      (node (ref "J2") (pin "3") (pinfunction "3_3") (pintype "bidirectional"))
      (node (ref "J2") (pin "5") (pinfunction "5_5") (pintype "bidirectional"))
      (node (ref "J4") (pin "A12_B1") (pinfunction "GND_A12_B1") (pintype "power_in"))
      (node (ref "J4") (pin "A1_B12") (pinfunction "GND_A1_B12") (pintype "power_in"))
      (node (ref "J4") (pin "SH1") (pinfunction "SHIELD_SH1") (pintype "passive"))
      (node (ref "J4") (pin "SH2") (pinfunction "SHIELD_SH2") (pintype "passive"))
      (node (ref "J4") (pin "SH3") (pinfunction "SHIELD_SH3") (pintype "passive"))
      (node (ref "J4") (pin "SH4") (pinfunction "SHIELD_SH4") (pintype "passive"))
      (node (ref "R1_USB") (pin "1") (pinfunction "1_1") (pintype "bidirectional"))
      (node (ref "R2_EP_DR") (pin "1") (pinfunction "1_1") (pintype "bidirectional"))
      (node (ref "R2_USB") (pin "2") (pinfunction "2_2") (pintype "bidirectional"))
      (node (ref "R3") (pin "1") (pinfunction "1_1") (pintype "bidirectional"))
      (node (ref "R9") (pin "1") (pinfunction "1_1") (pintype "bidirectional"))
      (node (ref "R_TYPE_SEL") (pin "1") (pinfunction "1_1") (pintype "bidirectional"))
      (node (ref "SJ1") (pin "1") (pinfunction "1_1") (pintype "passive"))
      (node (ref "SW_DN") (pin "1") (pinfunction "1_1") (pintype "passive"))
      (node (ref "SW_ENT") (pin "1") (pinfunction "1_1") (pintype "passive"))
      (node (ref "SW_UP") (pin "1") (pinfunction "1_1") (pintype "passive"))
      (node (ref "TP_BAT_GND") (pin "TP") (pinfunction "TP_TP") (pintype "input"))
      (node (ref "TP_GND") (pin "TP") (pinfunction "TP_TP") (pintype "input"))
      (node (ref "U1") (pin "P$74") (pinfunction "VSS_PAD_P$74") (pintype "bidirectional"))
      (node (ref "U1") (pin "P$75") (pinfunction "VSS_PAD_P$75") (pintype "bidirectional"))
      (node (ref "U1") (pin "P$76") (pinfunction "VSS_PAD_P$76") (pintype "bidirectional"))
      (node (ref "U1") (pin "P$77") (pinfunction "VSS_PAD_P$77") (pintype "bidirectional"))
      (node (ref "U1") (pin "P$78") (pinfunction "VSS_PAD_P$78") (pintype "bidirectional"))
      (node (ref "U1") (pin "P$79") (pinfunction "VSS_PAD_P$79") (pintype "bidirectional"))
      (node (ref "U1") (pin "P$80") (pinfunction "VSS_PAD_P$80") (pintype "bidirectional"))
      (node (ref "U1") (pin "P$81") (pinfunction "VSS_PAD_P$81") (pintype "bidirectional"))
      (node (ref "U1") (pin "P$82") (pinfunction "VSS_PAD_P$82") (pintype "bidirectional"))
      (node (ref "U1") (pin "P$83") (pinfunction "VSS_PAD_P$83") (pintype "bidirectional"))
      (node (ref "U1") (pin "P$84") (pinfunction "VSS_PAD_P$84") (pintype "bidirectional"))
      (node (ref "U1") (pin "P$85") (pinfunction "VSS_PAD_P$85") (pintype "bidirectional"))
      (node (ref "U1") (pin "P$86") (pinfunction "VSS_PAD_P$86") (pintype "bidirectional"))
      (node (ref "U1") (pin "P$87") (pinfunction "VSS_PAD_P$87") (pintype "bidirectional"))
      (node (ref "U1") (pin "P$88") (pinfunction "VSS_PAD_P$88") (pintype "bidirectional"))
      (node (ref "U1") (pin "P$89") (pinfunction "VSS_PAD_P$89") (pintype "bidirectional"))
      (node (ref "U1") (pin "P$90") (pinfunction "VSS_PAD_P$90") (pintype "bidirectional"))
      (node (ref "U1") (pin "P$B7") (pinfunction "VSS_P$B7") (pintype "power_in"))
      (node (ref "U1") (pin "P$F23") (pinfunction "VSS_PA_P$F23") (pintype "bidirectional"))
      (node (ref "U3") (pin "1") (pinfunction "CTG_1") (pintype "power_in"))
      (node (ref "U3") (pin "4") (pinfunction "GND_4") (pintype "power_in"))
      (node (ref "U3") (pin "6") (pinfunction "QSTRT_6") (pintype "input"))
      (node (ref "U3") (pin "9") (pinfunction "EP_9") (pintype "power_in"))
      (node (ref "X1") (pin "2") (pinfunction "2_2") (pintype "passive"))
      (node (ref "X1") (pin "4") (pinfunction "4_4") (pintype "passive"))
    )
    (net (code "25") (name "HAPTIC_EN{slash}1.4C") (class "Default")
      (node (ref "IC2") (pin "A1") (pinfunction "EN_A1") (pintype "bidirectional"))
    )
    (net (code "26") (name "HAPTIC_EN{slash}2.6A") (class "Default")
      (node (ref "U1") (pin "P$U1") (pinfunction "P0.12_P$U1") (pintype "bidirectional"))
    )
    (net (code "27") (name "IMU_INT1") (class "Default")
      (node (ref "IC3") (pin "5") (pinfunction "INT1_5") (pintype "bidirectional"))
      (node (ref "U1") (pin "P$N1") (pinfunction "P0.08_P$N1") (pintype "bidirectional"))
    )
    (net (code "28") (name "IMU_INT2") (class "Default")
      (node (ref "IC3") (pin "6") (pinfunction "INT2_6") (pintype "bidirectional"))
      (node (ref "U1") (pin "P$P2") (pinfunction "P1.08_P$P2") (pintype "bidirectional"))
    )
    (net (code "29") (name "LX1") (class "Default")
      (node (ref "IC9") (pin "B2") (pinfunction "SW1_1_B2") (pintype "bidirectional"))
      (node (ref "IC9") (pin "B3") (pinfunction "SW1_2_B3") (pintype "bidirectional"))
      (node (ref "L7") (pin "1") (pinfunction "1_1") (pintype "bidirectional"))
    )
    (net (code "30") (name "LX2") (class "Default")
      (node (ref "IC9") (pin "D2") (pinfunction "SW2_1_D2") (pintype "bidirectional"))
      (node (ref "IC9") (pin "D3") (pinfunction "SW2_2_D3") (pintype "bidirectional"))
      (node (ref "L7") (pin "2") (pinfunction "2_2") (pintype "bidirectional"))
    )
    (net (code "31") (name "MOSI{slash}1.5B") (class "Default")
      (node (ref "J1") (pin "14") (pinfunction "14_14") (pintype "bidirectional"))
    )
    (net (code "32") (name "MOSI{slash}2.2D") (class "Default")
      (node (ref "U1") (pin "P$B13") (pinfunction "P0.03/AIN1_P$B13") (pintype "bidirectional"))
    )
    (net (code "33") (name "Net-(D2-K)") (class "Default")
      (node (ref "C2-EP-DR") (pin "1") (pinfunction "1_1") (pintype "passive"))
      (node (ref "D2") (pin "1") (pinfunction "K_1") (pintype "bidirectional"))
      (node (ref "D4") (pin "2") (pinfunction "A_2") (pintype "bidirectional"))
    )
    (net (code "34") (name "Net-(D5-A)") (class "Default")
      (node (ref "C2-EP-DR") (pin "2") (pinfunction "2_2") (pintype "passive"))
      (node (ref "D5") (pin "2") (pinfunction "A_2") (pintype "bidirectional"))
      (node (ref "L5") (pin "2") (pinfunction "2_2") (pintype "passive"))
      (node (ref "Q3") (pin "3") (pinfunction "D_3") (pintype "bidirectional"))
    )
    (net (code "35") (name "Net-(EPD_C1-Pad2)") (class "Default")
      (node (ref "EPD_C1") (pin "2") (pinfunction "2_2") (pintype "passive"))
      (node (ref "J1") (pin "5") (pinfunction "5_5") (pintype "bidirectional"))
    )
    (net (code "36") (name "Net-(EPD_C2-Pad2)") (class "Default")
      (node (ref "EPD_C2") (pin "2") (pinfunction "2_2") (pintype "passive"))
      (node (ref "J1") (pin "4") (pinfunction "4_4") (pintype "bidirectional"))
    )
    (net (code "37") (name "Net-(EPD_C6-Pad2)") (class "Default")
      (node (ref "EPD_C6") (pin "2") (pinfunction "2_2") (pintype "passive"))
      (node (ref "J1") (pin "18") (pinfunction "18_18") (pintype "bidirectional"))
    )
    (net (code "38") (name "Net-(EPD_C7-Pad2)") (class "Default")
      (node (ref "EPD_C7") (pin "2") (pinfunction "2_2") (pintype "passive"))
      (node (ref "J1") (pin "19") (pinfunction "19_19") (pintype "bidirectional"))
    )
    (net (code "39") (name "Net-(EPD_C8-Pad2)") (class "Default")
      (node (ref "EPD_C8") (pin "2") (pinfunction "2_2") (pintype "passive"))
      (node (ref "J1") (pin "20") (pinfunction "20_20") (pintype "bidirectional"))
    )
    (net (code "40") (name "Net-(EPD_C10-Pad2)") (class "Default")
      (node (ref "EPD_C10") (pin "2") (pinfunction "2_2") (pintype "passive"))
      (node (ref "J1") (pin "22") (pinfunction "22_22") (pintype "bidirectional"))
    )
    (net (code "41") (name "Net-(EPD_C12-Pad2)") (class "Default")
      (node (ref "EPD_C12") (pin "2") (pinfunction "2_2") (pintype "passive"))
      (node (ref "J1") (pin "24") (pinfunction "24_24") (pintype "bidirectional"))
    )
    (net (code "42") (name "Net-(IC1-TS{slash}MR)") (class "Default")
      (node (ref "IC1") (pin "D1") (pinfunction "TS/MR_D1") (pintype "bidirectional"))
      (node (ref "R9") (pin "2") (pinfunction "2_2") (pintype "bidirectional"))
    )
    (net (code "43") (name "Net-(IC2-REG)") (class "Default")
      (node (ref "C32") (pin "2") (pinfunction "2_2") (pintype "passive"))
      (node (ref "IC2") (pin "A2") (pinfunction "REG_A2") (pintype "bidirectional"))
    )
    (net (code "44") (name "Net-(IC3-SDO)") (class "Default")
      (node (ref "IC3") (pin "1") (pinfunction "SDO_1") (pintype "bidirectional"))
      (node (ref "R3") (pin "2") (pinfunction "2_2") (pintype "bidirectional"))
    )
    (net (code "45") (name "Net-(IC9-SCL)") (class "Default")
      (node (ref "IC9") (pin "D1") (pinfunction "SCL_D1") (pintype "bidirectional"))
      (node (ref "R4") (pin "2") (pinfunction "2_2") (pintype "bidirectional"))
    )
    (net (code "46") (name "Net-(IC9-SDA)") (class "Default")
      (node (ref "IC9") (pin "E1") (pinfunction "SDA_E1") (pintype "bidirectional"))
      (node (ref "R2") (pin "2") (pinfunction "2_2") (pintype "bidirectional"))
    )
    (net (code "47") (name "Net-(J4-CC1)") (class "Default")
      (node (ref "J4") (pin "A5") (pinfunction "CC1_A5") (pintype "bidirectional"))
      (node (ref "R1_USB") (pin "2") (pinfunction "2_2") (pintype "bidirectional"))
    )
    (net (code "48") (name "Net-(J4-CC2)") (class "Default")
      (node (ref "J4") (pin "B5") (pinfunction "CC2_B5") (pintype "bidirectional"))
      (node (ref "R2_USB") (pin "1") (pinfunction "1_1") (pintype "bidirectional"))
    )
    (net (code "49") (name "Net-(L2-Pad2)") (class "Default")
      (node (ref "L2") (pin "2") (pinfunction "2_2") (pintype "passive"))
      (node (ref "L3") (pin "1") (pinfunction "1_1") (pintype "passive"))
    )
    (net (code "50") (name "Net-(R1_EP_DR-Pad1)") (class "Default")
      (node (ref "R1_EP_DR") (pin "1") (pinfunction "1_1") (pintype "bidirectional"))
      (node (ref "R_TYPE_SEL") (pin "2") (pinfunction "2_2") (pintype "bidirectional"))
      (node (ref "SJ1") (pin "2") (pinfunction "2_2") (pintype "passive"))
    )
    (net (code "51") (name "Net-(U1-ANT)") (class "Default")
      (node (ref "C3") (pin "1") (pinfunction "1_1") (pintype "passive"))
      (node (ref "L1") (pin "1") (pinfunction "1_1") (pintype "passive"))
      (node (ref "U1") (pin "P$H23") (pinfunction "ANT_P$H23") (pintype "bidirectional"))
    )
    (net (code "52") (name "Net-(U1-DCC)") (class "Default")
      (node (ref "L2") (pin "1") (pinfunction "1_1") (pintype "passive"))
      (node (ref "U1") (pin "P$B3") (pinfunction "DCC_P$B3") (pintype "output"))
    )
    (net (code "53") (name "Net-(U1-DEC2)") (class "Default")
      (node (ref "C13") (pin "1") (pinfunction "1_1") (pintype "passive"))
      (node (ref "U1") (pin "P$A18") (pinfunction "DEC2_P$A18") (pintype "bidirectional"))
    )
    (net (code "54") (name "Net-(U1-DEC3V3)") (class "Default")
      (node (ref "C20") (pin "1") (pinfunction "1_1") (pintype "passive"))
      (node (ref "U1") (pin "P$AC5") (pinfunction "DEC3V3_P$AC5") (pintype "bidirectional"))
    )
    (net (code "55") (name "Net-(U1-DEC5)") (class "Default")
      (node (ref "C9") (pin "1") (pinfunction "1_1") (pintype "passive"))
      (node (ref "U1") (pin "P$N24") (pinfunction "DEC5_P$N24") (pintype "bidirectional"))
    )
    (net (code "56") (name "Net-(U1-XC1)") (class "Default")
      (node (ref "C1") (pin "1") (pinfunction "1_1") (pintype "passive"))
      (node (ref "U1") (pin "P$B24") (pinfunction "XC1_P$B24") (pintype "input"))
      (node (ref "X1") (pin "1") (pinfunction "1_1") (pintype "passive"))
    )
    (net (code "57") (name "Net-(U1-XC2)") (class "Default")
      (node (ref "C2") (pin "1") (pinfunction "1_1") (pintype "passive"))
      (node (ref "U1") (pin "P$A23") (pinfunction "XC2_P$A23") (pintype "output"))
      (node (ref "X1") (pin "3") (pinfunction "3_3") (pintype "passive"))
    )
    (net (code "58") (name "OUT+") (class "Default")
      (node (ref "IC2") (pin "A3") (pinfunction "OUT+_A3") (pintype "bidirectional"))
      (node (ref "TP_OP") (pin "TP") (pinfunction "TP_TP") (pintype "input"))
    )
    (net (code "59") (name "OUT-") (class "Default")
      (node (ref "IC2") (pin "C3") (pinfunction "OUT-_C3") (pintype "bidirectional"))
      (node (ref "TP_ON") (pin "TP") (pinfunction "TP_TP") (pintype "input"))
    )
    (net (code "60") (name "P0.00{slash}XL1") (class "Default")
      (node (ref "C17") (pin "2") (pinfunction "2_2") (pintype "passive"))
      (node (ref "U1") (pin "P$D2") (pinfunction "P0.00/XL1_P$D2") (pintype "bidirectional"))
      (node (ref "X2") (pin "1") (pinfunction "1_1") (pintype "passive"))
    )
    (net (code "61") (name "P0.01{slash}XL2") (class "Default")
      (node (ref "C18") (pin "2") (pinfunction "2_2") (pintype "passive"))
      (node (ref "U1") (pin "P$F2") (pinfunction "P0.01/XL2_P$F2") (pintype "bidirectional"))
      (node (ref "X2") (pin "2") (pinfunction "2_2") (pintype "passive"))
    )
    (net (code "62") (name "P0.04") (class "Default")
      (node (ref "U1") (pin "P$J1") (pinfunction "P0.04/AIN2_P$J1") (pintype "bidirectional"))
    )
    (net (code "63") (name "P0.09") (class "Default")
      (node (ref "U1") (pin "P$L24") (pinfunction "P0.09/NFC1_P$L24") (pintype "bidirectional"))
    )
    (net (code "64") (name "P0.13{slash}1.5D") (class "Default")
      (node (ref "C30") (pin "2") (pinfunction "2_2") (pintype "passive"))
      (node (ref "R5") (pin "1") (pinfunction "1_1") (pintype "bidirectional"))
      (node (ref "SW_UP") (pin "2") (pinfunction "2_2") (pintype "passive"))
    )
    (net (code "65") (name "P0.13{slash}2.6C") (class "Default")
      (node (ref "U1") (pin "P$AD8") (pinfunction "P0.13_P$AD8") (pintype "bidirectional"))
    )
    (net (code "66") (name "P0.14{slash}1.5D") (class "Default")
      (node (ref "C31") (pin "2") (pinfunction "2_2") (pintype "passive"))
      (node (ref "R8") (pin "1") (pinfunction "1_1") (pintype "bidirectional"))
      (node (ref "SW_ENT") (pin "2") (pinfunction "2_2") (pintype "passive"))
    )
    (net (code "67") (name "P0.14{slash}2.7C") (class "Default")
      (node (ref "U1") (pin "P$AC9") (pinfunction "P0.14_P$AC9") (pintype "bidirectional"))
    )
    (net (code "68") (name "P0.19") (class "Default")
      (node (ref "U1") (pin "P$AC15") (pinfunction "P0.19_P$AC15") (pintype "bidirectional"))
    )
    (net (code "69") (name "P0.20") (class "Default")
      (node (ref "U1") (pin "P$AD16") (pinfunction "P0.20_P$AD16") (pintype "bidirectional"))
    )
    (net (code "70") (name "P0.21") (class "Default")
      (node (ref "U1") (pin "P$AC17") (pinfunction "P0.21_P$AC17") (pintype "bidirectional"))
    )
    (net (code "71") (name "P0.22") (class "Default")
      (node (ref "U1") (pin "P$AD18") (pinfunction "P0.22_P$AD18") (pintype "bidirectional"))
    )
    (net (code "72") (name "P0.23") (class "Default")
      (node (ref "U1") (pin "P$AC19") (pinfunction "P0.23_P$AC19") (pintype "bidirectional"))
    )
    (net (code "73") (name "P0.24") (class "Default")
      (node (ref "U1") (pin "P$AD20") (pinfunction "P0.24_P$AD20") (pintype "bidirectional"))
    )
    (net (code "74") (name "P0.25") (class "Default")
      (node (ref "U1") (pin "P$AC21") (pinfunction "P0.25_P$AC21") (pintype "bidirectional"))
    )
    (net (code "75") (name "P0.26") (class "Default")
      (node (ref "U1") (pin "P$G1") (pinfunction "P0.26_P$G1") (pintype "bidirectional"))
    )
    (net (code "76") (name "P0.27") (class "Default")
      (node (ref "U1") (pin "P$H2") (pinfunction "P0.27_P$H2") (pintype "bidirectional"))
    )
    (net (code "77") (name "P0.28") (class "Default")
      (node (ref "U1") (pin "P$B11") (pinfunction "P0.28/AIN4_P$B11") (pintype "bidirectional"))
    )
    (net (code "78") (name "P0.29") (class "Default")
      (node (ref "U1") (pin "P$A10") (pinfunction "P0.29/AIN5_P$A10") (pintype "bidirectional"))
    )
    (net (code "79") (name "P0.30") (class "Default")
      (node (ref "U1") (pin "P$B9") (pinfunction "P0.30/AIN6_P$B9") (pintype "bidirectional"))
    )
    (net (code "80") (name "P0.31") (class "Default")
      (node (ref "U1") (pin "P$A8") (pinfunction "P0.31/AIN7_P$A8") (pintype "bidirectional"))
    )
    (net (code "81") (name "P1.01{slash}1.6C") (class "Default")
      (node (ref "DMG2305UX-7") (pin "1") (pinfunction "G_1") (pintype "bidirectional"))
      (node (ref "R_PWR_EPD") (pin "1") (pinfunction "1_1") (pintype "bidirectional"))
    )
    (net (code "82") (name "P1.01{slash}2.4B") (class "Default")
      (node (ref "U1") (pin "P$Y23") (pinfunction "P1.01_P$Y23") (pintype "bidirectional"))
    )
    (net (code "83") (name "P1.02{slash}1.6C") (class "Default")
      (node (ref "C29") (pin "2") (pinfunction "2_2") (pintype "passive"))
      (node (ref "R7") (pin "1") (pinfunction "1_1") (pintype "bidirectional"))
      (node (ref "SW_DN") (pin "2") (pinfunction "2_2") (pintype "passive"))
    )
    (net (code "84") (name "P1.02{slash}2.8C") (class "Default")
      (node (ref "U1") (pin "P$W24") (pinfunction "P1.02_P$W24") (pintype "bidirectional"))
    )
    (net (code "85") (name "P1.03") (class "Default")
      (node (ref "U1") (pin "P$V23") (pinfunction "P1.03_P$V23") (pintype "bidirectional"))
    )
    (net (code "86") (name "P1.04") (class "Default")
      (node (ref "U1") (pin "P$U24") (pinfunction "P1.04_P$U24") (pintype "bidirectional"))
    )
    (net (code "87") (name "P1.05") (class "Default")
      (node (ref "U1") (pin "P$T23") (pinfunction "P1.05_P$T23") (pintype "bidirectional"))
    )
    (net (code "88") (name "P1.06") (class "Default")
      (node (ref "U1") (pin "P$R24") (pinfunction "P1.06_P$R24") (pintype "bidirectional"))
    )
    (net (code "89") (name "P1.07") (class "Default")
      (node (ref "U1") (pin "P$P23") (pinfunction "P1.07_P$P23") (pintype "bidirectional"))
    )
    (net (code "90") (name "P1.09") (class "Default")
      (node (ref "U1") (pin "P$R1") (pinfunction "P1.09_P$R1") (pintype "bidirectional"))
    )
    (net (code "91") (name "P1.10") (class "Default")
      (node (ref "U1") (pin "P$A20") (pinfunction "P1.10_P$A20") (pintype "bidirectional"))
    )
    (net (code "92") (name "P1.11") (class "Default")
      (node (ref "U1") (pin "P$B19") (pinfunction "P1.11_P$B19") (pintype "bidirectional"))
    )
    (net (code "93") (name "P1.12") (class "Default")
      (node (ref "U1") (pin "P$B17") (pinfunction "P1.12_P$B17") (pintype "bidirectional"))
    )
    (net (code "94") (name "P1.13") (class "Default")
      (node (ref "U1") (pin "P$A16") (pinfunction "P1.13_P$A16") (pintype "bidirectional"))
    )
    (net (code "95") (name "P1.14") (class "Default")
      (node (ref "U1") (pin "P$B15") (pinfunction "P1.14_P$B15") (pintype "bidirectional"))
    )
    (net (code "96") (name "P1.15") (class "Default")
      (node (ref "U1") (pin "P$A14") (pinfunction "P1.15_P$A14") (pintype "bidirectional"))
    )
    (net (code "97") (name "PMIC_INT") (class "Default")
      (node (ref "IC1") (pin "A1") (pinfunction "~{INT}_A1") (pintype "bidirectional"))
      (node (ref "U1") (pin "P$T2") (pinfunction "P0.11_P$T2") (pintype "bidirectional"))
    )
    (net (code "98") (name "PREVGH") (class "Default")
      (node (ref "D5") (pin "1") (pinfunction "K_1") (pintype "bidirectional"))
      (node (ref "EPD_C9") (pin "2") (pinfunction "2_2") (pintype "passive"))
      (node (ref "J1") (pin "21") (pinfunction "21_21") (pintype "bidirectional"))
    )
    (net (code "99") (name "PREVGL") (class "Default")
      (node (ref "D2") (pin "2") (pinfunction "A_2") (pintype "bidirectional"))
      (node (ref "EPD_C11") (pin "2") (pinfunction "2_2") (pintype "passive"))
      (node (ref "J1") (pin "23") (pinfunction "23_23") (pintype "bidirectional"))
    )
    (net (code "100") (name "RESE") (class "Default")
      (node (ref "J1") (pin "3") (pinfunction "3_3") (pintype "bidirectional"))
      (node (ref "Q3") (pin "2") (pinfunction "S_2") (pintype "bidirectional"))
      (node (ref "R1_EP_DR") (pin "2") (pinfunction "2_2") (pintype "bidirectional"))
    )
    (net (code "101") (name "RESET") (class "Default")
      (node (ref "J2") (pin "6") (pinfunction "6_6") (pintype "bidirectional"))
      (node (ref "TP_RESET") (pin "TP") (pinfunction "TP_TP") (pintype "input"))
      (node (ref "U1") (pin "P$AC13") (pinfunction "P0.18/RESET_P$AC13") (pintype "bidirectional"))
    )
    (net (code "102") (name "RF") (class "Default")
      (node (ref "ANT1") (pin "1") (pinfunction "FEED_1") (pintype "input"))
      (node (ref "C22") (pin "1") (pinfunction "1_1") (pintype "passive"))
      (node (ref "C4") (pin "1") (pinfunction "1_1") (pintype "passive"))
      (node (ref "L1") (pin "2") (pinfunction "2_2") (pintype "passive"))
    )
    (net (code "103") (name "SCK{slash}1.5B") (class "Default")
      (node (ref "J1") (pin "13") (pinfunction "13_13") (pintype "bidirectional"))
    )
    (net (code "104") (name "SCK{slash}2.2D") (class "Default")
      (node (ref "U1") (pin "P$A12") (pinfunction "P0.02/AIN0_P$A12") (pintype "bidirectional"))
    )
    (net (code "105") (name "SCL{slash}1.4C") (class "Default")
      (node (ref "IC2") (pin "C1") (pinfunction "SCL_C1") (pintype "bidirectional"))
      (node (ref "U3") (pin "7") (pinfunction "SCL_7") (pintype "input"))
    )
    (net (code "106") (name "SCL{slash}2.4C") (class "Default")
      (node (ref "IC1") (pin "B1") (pinfunction "SCL_B1") (pintype "bidirectional"))
      (node (ref "IC3") (pin "12") (pinfunction "SCX_12") (pintype "bidirectional"))
      (node (ref "R17") (pin "2") (pinfunction "2_2") (pintype "bidirectional"))
      (node (ref "R4") (pin "1") (pinfunction "1_1") (pintype "bidirectional"))
      (node (ref "TP_SCL") (pin "TP") (pinfunction "TP_TP") (pintype "input"))
      (node (ref "U1") (pin "P$M2") (pinfunction "P0.07_P$M2") (pintype "bidirectional"))
    )
    (net (code "107") (name "SDA{slash}1.4C") (class "Default")
      (node (ref "IC2") (pin "B2") (pinfunction "SDA_B2") (pintype "bidirectional"))
      (node (ref "U3") (pin "8") (pinfunction "SDA_8") (pintype "bidirectional"))
    )
    (net (code "108") (name "SDA{slash}2.4C") (class "Default")
      (node (ref "IC1") (pin "C1") (pinfunction "SDA_C1") (pintype "bidirectional"))
      (node (ref "IC3") (pin "2") (pinfunction "SDX_2") (pintype "bidirectional"))
      (node (ref "R18") (pin "2") (pinfunction "2_2") (pintype "bidirectional"))
      (node (ref "R2") (pin "1") (pinfunction "1_1") (pintype "bidirectional"))
      (node (ref "TP_SDA") (pin "TP") (pinfunction "TP_TP") (pintype "input"))
      (node (ref "U1") (pin "P$L1") (pinfunction "P0.06_P$L1") (pintype "bidirectional"))
    )
    (net (code "109") (name "SWDCLK") (class "Default")
      (node (ref "J2") (pin "4") (pinfunction "4_4") (pintype "bidirectional"))
      (node (ref "TP_SWDCLK") (pin "TP") (pinfunction "TP_TP") (pintype "input"))
      (node (ref "U1") (pin "P$AA24") (pinfunction "SWDCLK_P$AA24") (pintype "input"))
    )
    (net (code "110") (name "SWDIO") (class "Default")
      (node (ref "J2") (pin "2") (pinfunction "2_2") (pintype "bidirectional"))
      (node (ref "TP_SWDIO") (pin "TP") (pinfunction "TP_TP") (pintype "input"))
      (node (ref "U1") (pin "P$AC24") (pinfunction "SWDIO_P$AC24") (pintype "bidirectional"))
    )
    (net (code "111") (name "SWO") (class "Default")
      (node (ref "TP_SWO") (pin "TP") (pinfunction "TP_TP") (pintype "input"))
      (node (ref "U1") (pin "P$AD22") (pinfunction "P1.00_P$AD22") (pintype "bidirectional"))
    )
    (net (code "112") (name "VBAT{slash}1.2A") (class "Default")
      (node (ref "C27") (pin "2") (pinfunction "2_2") (pintype "passive"))
      (node (ref "TP_VBAT") (pin "TP") (pinfunction "TP_TP") (pintype "input"))
      (node (ref "U3") (pin "2") (pinfunction "CELL_2") (pintype "power_in"))
      (node (ref "U3") (pin "3") (pinfunction "VDD_3") (pintype "power_in"))
    )
    (net (code "113") (name "VBAT{slash}2.5C") (class "Default")
      (node (ref "C37") (pin "2") (pinfunction "2_2") (pintype "passive"))
      (node (ref "IC1") (pin "C2") (pinfunction "BAT_C2") (pintype "bidirectional"))
    )
    (net (code "114") (name "VBUS{slash}1.5D") (class "Default")
      (node (ref "C42") (pin "1") (pinfunction "1_1") (pintype "passive"))
      (node (ref "C43") (pin "1") (pinfunction "1_1") (pintype "passive"))
      (node (ref "D3") (pin "5") (pinfunction "VBUS_5") (pintype "bidirectional"))
      (node (ref "J4") (pin "A4_B9") (pinfunction "VBUS_A4_B9") (pintype "power_in"))
      (node (ref "J4") (pin "A9_B4") (pinfunction "VBUS_A9_B4") (pintype "power_in"))
    )
    (net (code "115") (name "VBUS{slash}2.6D") (class "Default")
      (node (ref "C21") (pin "1") (pinfunction "1_1") (pintype "passive"))
      (node (ref "C38") (pin "2") (pinfunction "2_2") (pintype "passive"))
      (node (ref "IC1") (pin "A2") (pinfunction "IN_A2") (pintype "bidirectional"))
      (node (ref "U1") (pin "P$AD2") (pinfunction "VBUS_P$AD2") (pintype "power_in"))
    )
    (net (code "116") (name "VREG") (class "Default")
      (node (ref "C23") (pin "2") (pinfunction "2_2") (pintype "passive"))
      (node (ref "C24") (pin "2") (pinfunction "2_2") (pintype "passive"))
      (node (ref "C39") (pin "1") (pinfunction "1_1") (pintype "passive"))
      (node (ref "IC1") (pin "B2") (pinfunction "SYS_B2") (pintype "bidirectional"))
      (node (ref "IC9") (pin "A1") (pinfunction "EN_A1") (pintype "bidirectional"))
      (node (ref "IC9") (pin "A2") (pinfunction "VIN_1_A2") (pintype "bidirectional"))
      (node (ref "IC9") (pin "A3") (pinfunction "VIN_2_A3") (pintype "bidirectional"))
      (node (ref "TP_VREG") (pin "TP") (pinfunction "TP_TP") (pintype "input"))
    )
    (net (code "117") (name "unconnected-(ANT1-NC-Pad2)") (class "Default")
      (node (ref "ANT1") (pin "2") (pinfunction "NC_2") (pintype "no_connect"))
    )
    (net (code "118") (name "unconnected-(IC3-ASCL-Pad11)") (class "Default")
      (node (ref "IC3") (pin "11") (pinfunction "ASCL_11") (pintype "bidirectional"))
    )
    (net (code "119") (name "unconnected-(IC3-ASDA-Pad4)") (class "Default")
      (node (ref "IC3") (pin "4") (pinfunction "ASDA_4") (pintype "bidirectional"))
    )
    (net (code "120") (name "unconnected-(J1-Pad1)") (class "Default")
      (node (ref "J1") (pin "1") (pinfunction "1_1") (pintype "bidirectional"))
    )
    (net (code "121") (name "unconnected-(J1-Pad6)") (class "Default")
      (node (ref "J1") (pin "6") (pinfunction "6_6") (pintype "bidirectional"))
    )
    (net (code "122") (name "unconnected-(J1-Pad7)") (class "Default")
      (node (ref "J1") (pin "7") (pinfunction "7_7") (pintype "bidirectional"))
    )
    (net (code "123") (name "unconnected-(J4-SBU1-PadA8)") (class "Default")
      (node (ref "J4") (pin "A8") (pinfunction "SBU1_A8") (pintype "bidirectional"))
    )
    (net (code "124") (name "unconnected-(J4-SBU2-PadB8)") (class "Default")
      (node (ref "J4") (pin "B8") (pinfunction "SBU2_B8") (pintype "bidirectional"))
    )
    (net (code "125") (name "unconnected-(U1-DCCH-PadP$AB2)") (class "Default")
      (node (ref "U1") (pin "P$AB2") (pinfunction "DCCH_P$AB2") (pintype "bidirectional"))
    )
  )
)
